# peroherals.net
KiCad netlist of a schematic drawn in Altium Designer
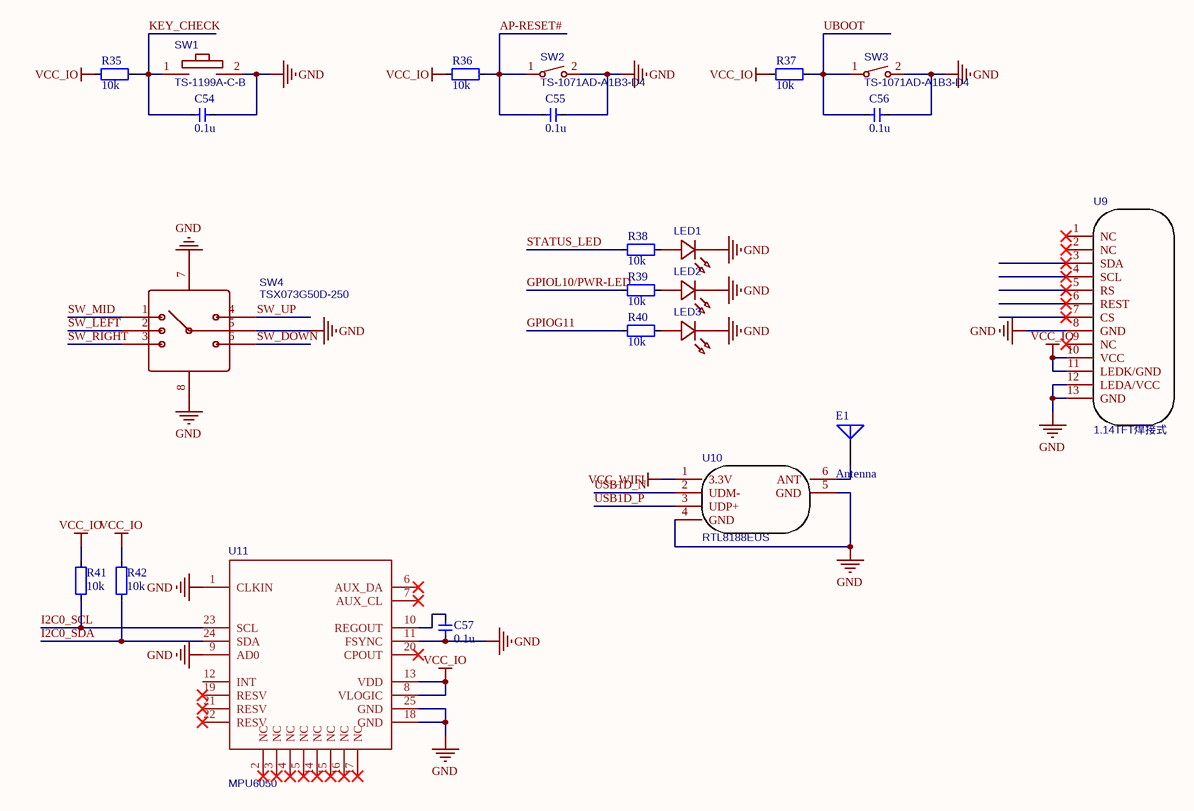
[diagram p0: peroherals.SchDoc]

(export (version "E")
  (design (tool "Eeschema 10.0.6"))
  (components
    (comp (ref "C54")
      (value "0.1u")
      (footprint "C0402")
      (description "Capacitor")
      (fields (field (name "Comment") "CAP-0402"))
      (libsource (lib "core") (part "CAP-0402"))
    )
    (comp (ref "C55")
      (value "0.1u")
      (footprint "C0402")
      (description "Capacitor")
      (fields (field (name "Comment") "CAP-0402"))
      (libsource (lib "core") (part "CAP-0402"))
    )
    (comp (ref "C56")
      (value "0.1u")
      (footprint "C0402")
      (description "Capacitor")
      (fields (field (name "Comment") "CAP-0402"))
      (libsource (lib "core") (part "CAP-0402"))
    )
    (comp (ref "C57")
      (value "0.1u")
      (footprint "C0402")
      (description "Capacitor")
      (fields (field (name "Comment") "CAP-0402"))
      (libsource (lib "core") (part "CAP-0402"))
    )
    (comp (ref "E1")
      (value "Antenna")
      (footprint "PIN1")
      (description "Generic Antenna")
      (fields (field (name "PUBLISHER") "Altium Limited"))
      (libsource (lib "Miscellaneous Devices") (part "Antenna"))
    )
    (comp (ref "LED1")
      (value "TJ-S1005CL4T5ALC6B-A5")
      (footprint "LED0402-RD")
      (fields (field (name "BOM_SUPPLIER PART") "C917189") (field (name "CONTRIBUTOR") "LCSC"))
      (libsource (lib "core") (part "LED-0402"))
    )
    (comp (ref "LED2")
      (value "TJ-S1005CL4T5ALC6B-A5")
      (footprint "LED0402-RD")
      (fields (field (name "BOM_SUPPLIER PART") "C917189") (field (name "CONTRIBUTOR") "LCSC"))
      (libsource (lib "core") (part "LED-0402"))
    )
    (comp (ref "LED3")
      (value "TJ-S1005CL4T5ALC6B-A5")
      (footprint "LED0402-RD")
      (fields (field (name "BOM_SUPPLIER PART") "C917189") (field (name "CONTRIBUTOR") "LCSC"))
      (libsource (lib "core") (part "LED-0402"))
    )
    (comp (ref "R35")
      (value "10k")
      (footprint "R0402")
      (description "Resistor")
      (fields (field (name "Comment") "RES-0402"))
      (libsource (lib "") (part "RES-0402_1"))
    )
    (comp (ref "R36")
      (value "10k")
      (footprint "R0402")
      (description "Resistor")
      (fields (field (name "Comment") "RES-0402"))
      (libsource (lib "") (part "RES-0402_1"))
    )
    (comp (ref "R37")
      (value "10k")
      (footprint "R0402")
      (description "Resistor")
      (fields (field (name "Comment") "RES-0402"))
      (libsource (lib "") (part "RES-0402_1"))
    )
    (comp (ref "R38")
      (value "10k")
      (footprint "R0402")
      (description "Resistor")
      (fields (field (name "Comment") "RES-0402"))
      (libsource (lib "") (part "RES-0402_1"))
    )
    (comp (ref "R39")
      (value "10k")
      (footprint "R0402")
      (description "Resistor")
      (fields (field (name "Comment") "RES-0402"))
      (libsource (lib "") (part "RES-0402_1"))
    )
    (comp (ref "R40")
      (value "10k")
      (footprint "R0402")
      (description "Resistor")
      (fields (field (name "Comment") "RES-0402"))
      (libsource (lib "") (part "RES-0402_1"))
    )
    (comp (ref "R41")
      (value "10k")
      (footprint "R0402")
      (description "Resistor")
      (fields (field (name "Comment") "RES-0402"))
      (libsource (lib "core") (part "RES-0402"))
    )
    (comp (ref "R42")
      (value "10k")
      (footprint "R0402")
      (description "Resistor")
      (fields (field (name "Comment") "RES-0402"))
      (libsource (lib "core") (part "RES-0402"))
    )
    (comp (ref "SW1")
      (value "TS-1199A-C-B")
      (footprint "KEY-SMD_2P-L6.0-W6.0-P6.50")
      (fields (field (name "BOM_SUPPLIER PART") "C318880") (field (name "CONTRIBUTOR") "LCSC"))
      (libsource (lib "core") (part "TS-1199A-C-B"))
    )
    (comp (ref "SW2")
      (value "TS-1071AD-A1B3-D4")
      (footprint "ButtonTACT_3x4x2_180")
      (fields (field (name "BOM_SUPPLIER PART") "C492878") (field (name "CONTRIBUTOR") "LCSC"))
      (libsource (lib "core") (part "TS-1071AD-A1B3-D4"))
    )
    (comp (ref "SW3")
      (value "TS-1071AD-A1B3-D4")
      (footprint "ButtonTACT_3x4x2_180")
      (fields (field (name "BOM_SUPPLIER PART") "C492878") (field (name "CONTRIBUTOR") "LCSC"))
      (libsource (lib "core") (part "TS-1071AD-A1B3-D4"))
    )
    (comp (ref "SW4")
      (value "TSX073G50D-250")
      (footprint "SW-SMD_TSX073G50D1-250")
      (fields (field (name "BOM_SUPPLIER PART") "C722953") (field (name "CONTRIBUTOR") "LCSC"))
      (libsource (lib "core") (part "TSX073G50D-250"))
    )
    (comp (ref "U9")
      (value "1.14TFT焊接式")
      (footprint "1.14TFT焊接式B")
      (fields (field (name "BOM_MANUFACTURER PART") "1.14寸LCD") (field (name "CONTRIBUTOR") "lanlanzhilian"))
      (libsource (lib "core") (part "1.14TFT焊接式"))
    )
    (comp (ref "U10")
      (value "RTL8188EUS")
      (footprint "USB-WIFI-ANT")
      (fields (field (name "CONTRIBUTOR") "Robin00"))
      (libsource (lib "core") (part "RTL8188EUS"))
    )
    (comp (ref "U11")
      (value "MPU6050")
      (footprint "QFN50P400X400X95-25T265X275N")
      (libsource (lib "core") (part "MPU6050"))
    )
  )
  (nets
    (net (code "1") (name "/AP-RESET#") (class "Default")
      (node (ref "C55") (pin "2") (pinfunction "2_2") (pintype "passive"))
      (node (ref "R36") (pin "1") (pinfunction "1_1") (pintype "passive"))
      (node (ref "SW2") (pin "1") (pinfunction "1_1") (pintype "passive"))
    )
    (net (code "2") (name "/GPIOG11") (class "Default")
      (node (ref "R40") (pin "2") (pinfunction "2_2") (pintype "passive"))
    )
    (net (code "3") (name "/GPIOL10{slash}PWR-LED") (class "Default")
      (node (ref "R39") (pin "2") (pinfunction "2_2") (pintype "passive"))
    )
    (net (code "4") (name "/I2C0_SCL") (class "Default")
      (node (ref "R41") (pin "2") (pinfunction "2_2") (pintype "passive"))
      (node (ref "U11") (pin "23") (pinfunction "SCL_23") (pintype "passive"))
    )
    (net (code "5") (name "/I2C0_SDA") (class "Default")
      (node (ref "R42") (pin "2") (pinfunction "2_2") (pintype "passive"))
      (node (ref "U11") (pin "24") (pinfunction "SDA_24") (pintype "passive"))
    )
    (net (code "6") (name "/KEY_CHECK") (class "Default")
      (node (ref "C54") (pin "2") (pinfunction "2_2") (pintype "passive"))
      (node (ref "R35") (pin "1") (pinfunction "1_1") (pintype "passive"))
      (node (ref "SW1") (pin "1") (pinfunction "1_1") (pintype "passive"))
    )
    (net (code "7") (name "/STATUS_LED") (class "Default")
      (node (ref "R38") (pin "2") (pinfunction "2_2") (pintype "passive"))
    )
    (net (code "8") (name "/SW_DOWN") (class "Default")
      (node (ref "SW4") (pin "6") (pinfunction "C_6") (pintype "passive"))
    )
    (net (code "9") (name "/SW_LEFT") (class "Default")
      (node (ref "SW4") (pin "2") (pinfunction "CENTER_2") (pintype "passive"))
    )
    (net (code "10") (name "/SW_MID") (class "Default")
      (node (ref "SW4") (pin "1") (pinfunction "A_1") (pintype "passive"))
    )
    (net (code "11") (name "/SW_RIGHT") (class "Default")
      (node (ref "SW4") (pin "3") (pinfunction "B_3") (pintype "passive"))
    )
    (net (code "12") (name "/SW_UP") (class "Default")
      (node (ref "SW4") (pin "4") (pinfunction "D_4") (pintype "passive"))
    )
    (net (code "13") (name "/UBOOT") (class "Default")
      (node (ref "C56") (pin "2") (pinfunction "2_2") (pintype "passive"))
      (node (ref "R37") (pin "1") (pinfunction "1_1") (pintype "passive"))
      (node (ref "SW3") (pin "1") (pinfunction "1_1") (pintype "passive"))
    )
    (net (code "14") (name "/USB1D_N") (class "Default")
      (node (ref "U10") (pin "2") (pinfunction "UDM-_2") (pintype "passive"))
    )
    (net (code "15") (name "/USB1D_P") (class "Default")
      (node (ref "U10") (pin "3") (pinfunction "UDP+_3") (pintype "passive"))
    )
    (net (code "16") (name "GND") (class "Default")
      (node (ref "C54") (pin "1") (pinfunction "1_1") (pintype "passive"))
      (node (ref "C55") (pin "1") (pinfunction "1_1") (pintype "passive"))
      (node (ref "C56") (pin "1") (pinfunction "1_1") (pintype "passive"))
      (node (ref "C57") (pin "2") (pinfunction "2_2") (pintype "passive"))
      (node (ref "LED1") (pin "1") (pinfunction "K_1") (pintype "passive"))
      (node (ref "LED2") (pin "1") (pinfunction "K_1") (pintype "passive"))
      (node (ref "LED3") (pin "1") (pinfunction "K_1") (pintype "passive"))
      (node (ref "SW1") (pin "2") (pinfunction "2_2") (pintype "passive"))
      (node (ref "SW2") (pin "2") (pinfunction "2_2") (pintype "passive"))
      (node (ref "SW3") (pin "2") (pinfunction "2_2") (pintype "passive"))
      (node (ref "SW4") (pin "5") (pinfunction "COM_5") (pintype "passive"))
      (node (ref "SW4") (pin "7") (pinfunction "GND_7") (pintype "passive"))
      (node (ref "SW4") (pin "8") (pinfunction "GND_8") (pintype "passive"))
      (node (ref "U10") (pin "4") (pinfunction "GND_4") (pintype "passive"))
      (node (ref "U10") (pin "5") (pinfunction "GND_5") (pintype "passive"))
      (node (ref "U11") (pin "1") (pinfunction "CLKIN_1") (pintype "passive"))
      (node (ref "U11") (pin "11") (pinfunction "FSYNC_11") (pintype "passive"))
      (node (ref "U11") (pin "18") (pinfunction "GND_18") (pintype "passive"))
      (node (ref "U11") (pin "25") (pinfunction "GND_25") (pintype "passive"))
      (node (ref "U11") (pin "9") (pinfunction "AD0_9") (pintype "passive"))
      (node (ref "U9") (pin "12") (pinfunction "LEDA/VCC_12") (pintype "passive"))
      (node (ref "U9") (pin "13") (pinfunction "GND_13") (pintype "passive"))
      (node (ref "U9") (pin "8") (pinfunction "GND_8") (pintype "passive"))
    )
    (net (code "17") (name "Net-(E1-A)") (class "Default")
      (node (ref "E1") (pin "1") (pinfunction "A_1") (pintype "passive"))
      (node (ref "U10") (pin "6") (pinfunction "ANT_6") (pintype "passive"))
    )
    (net (code "18") (name "Net-(LED1-A)") (class "Default")
      (node (ref "LED1") (pin "2") (pinfunction "A_2") (pintype "passive"))
      (node (ref "R38") (pin "1") (pinfunction "1_1") (pintype "passive"))
    )
    (net (code "19") (name "Net-(LED2-A)") (class "Default")
      (node (ref "LED2") (pin "2") (pinfunction "A_2") (pintype "passive"))
      (node (ref "R39") (pin "1") (pinfunction "1_1") (pintype "passive"))
    )
    (net (code "20") (name "Net-(LED3-A)") (class "Default")
      (node (ref "LED3") (pin "2") (pinfunction "A_2") (pintype "passive"))
      (node (ref "R40") (pin "1") (pinfunction "1_1") (pintype "passive"))
    )
    (net (code "21") (name "Net-(U11-REGOUT)") (class "Default")
      (node (ref "C57") (pin "1") (pinfunction "1_1") (pintype "passive"))
      (node (ref "U11") (pin "10") (pinfunction "REGOUT_10") (pintype "passive"))
    )
    (net (code "22") (name "VCC_IO") (class "Default")
      (node (ref "R35") (pin "2") (pinfunction "2_2") (pintype "passive"))
      (node (ref "R36") (pin "2") (pinfunction "2_2") (pintype "passive"))
      (node (ref "R37") (pin "2") (pinfunction "2_2") (pintype "passive"))
      (node (ref "R41") (pin "1") (pinfunction "1_1") (pintype "passive"))
      (node (ref "R42") (pin "1") (pinfunction "1_1") (pintype "passive"))
      (node (ref "U11") (pin "13") (pinfunction "VDD_13") (pintype "passive"))
      (node (ref "U11") (pin "8") (pinfunction "VLOGIC_8") (pintype "passive"))
      (node (ref "U9") (pin "10") (pinfunction "VCC_10") (pintype "passive"))
      (node (ref "U9") (pin "11") (pinfunction "LEDK/GND_11") (pintype "passive"))
    )
    (net (code "23") (name "VCC_WIFI") (class "Default")
      (node (ref "U10") (pin "1") (pinfunction "3.3V_1") (pintype "passive"))
    )
    (net (code "24") (name "unconnected-(U9-CS-Pad7)") (class "Default")
      (node (ref "U9") (pin "7") (pinfunction "CS_7") (pintype "passive+no_connect"))
    )
    (net (code "25") (name "unconnected-(U9-NC-Pad1)") (class "Default")
      (node (ref "U9") (pin "1") (pinfunction "NC_1") (pintype "passive+no_connect"))
    )
    (net (code "26") (name "unconnected-(U9-NC-Pad2)") (class "Default")
      (node (ref "U9") (pin "2") (pinfunction "NC_2") (pintype "passive+no_connect"))
    )
    (net (code "27") (name "unconnected-(U9-NC-Pad9)") (class "Default")
      (node (ref "U9") (pin "9") (pinfunction "NC_9") (pintype "passive+no_connect"))
    )
    (net (code "28") (name "unconnected-(U9-REST-Pad6)") (class "Default")
      (node (ref "U9") (pin "6") (pinfunction "REST_6") (pintype "passive+no_connect"))
    )
    (net (code "29") (name "unconnected-(U9-RS-Pad5)") (class "Default")
      (node (ref "U9") (pin "5") (pinfunction "RS_5") (pintype "passive+no_connect"))
    )
    (net (code "30") (name "unconnected-(U9-SCL-Pad4)") (class "Default")
      (node (ref "U9") (pin "4") (pinfunction "SCL_4") (pintype "passive+no_connect"))
    )
    (net (code "31") (name "unconnected-(U9-SDA-Pad3)") (class "Default")
      (node (ref "U9") (pin "3") (pinfunction "SDA_3") (pintype "passive+no_connect"))
    )
    (net (code "32") (name "unconnected-(U11-AUX_CL-Pad7)") (class "Default")
      (node (ref "U11") (pin "7") (pinfunction "AUX_CL_7") (pintype "passive+no_connect"))
    )
    (net (code "33") (name "unconnected-(U11-AUX_DA-Pad6)") (class "Default")
      (node (ref "U11") (pin "6") (pinfunction "AUX_DA_6") (pintype "passive+no_connect"))
    )
    (net (code "34") (name "unconnected-(U11-CPOUT-Pad20)") (class "Default")
      (node (ref "U11") (pin "20") (pinfunction "CPOUT_20") (pintype "passive+no_connect"))
    )
    (net (code "35") (name "unconnected-(U11-INT-Pad12)") (class "Default")
      (node (ref "U11") (pin "12") (pinfunction "INT_12") (pintype "passive"))
    )
    (net (code "36") (name "unconnected-(U11-NC-Pad2)") (class "Default")
      (node (ref "U11") (pin "2") (pinfunction "NC_2") (pintype "passive+no_connect"))
    )
    (net (code "37") (name "unconnected-(U11-NC-Pad3)") (class "Default")
      (node (ref "U11") (pin "3") (pinfunction "NC_3") (pintype "passive+no_connect"))
    )
    (net (code "38") (name "unconnected-(U11-NC-Pad4)") (class "Default")
      (node (ref "U11") (pin "4") (pinfunction "NC_4") (pintype "passive+no_connect"))
    )
    (net (code "39") (name "unconnected-(U11-NC-Pad5)") (class "Default")
      (node (ref "U11") (pin "5") (pinfunction "NC_5") (pintype "passive+no_connect"))
    )
    (net (code "40") (name "unconnected-(U11-NC-Pad14)") (class "Default")
      (node (ref "U11") (pin "14") (pinfunction "NC_14") (pintype "passive+no_connect"))
    )
    (net (code "41") (name "unconnected-(U11-NC-Pad15)") (class "Default")
      (node (ref "U11") (pin "15") (pinfunction "NC_15") (pintype "passive+no_connect"))
    )
    (net (code "42") (name "unconnected-(U11-NC-Pad16)") (class "Default")
      (node (ref "U11") (pin "16") (pinfunction "NC_16") (pintype "passive+no_connect"))
    )
    (net (code "43") (name "unconnected-(U11-NC-Pad17)") (class "Default")
      (node (ref "U11") (pin "17") (pinfunction "NC_17") (pintype "passive+no_connect"))
    )
    (net (code "44") (name "unconnected-(U11-RESV-Pad19)") (class "Default")
      (node (ref "U11") (pin "19") (pinfunction "RESV_19") (pintype "passive+no_connect"))
    )
    (net (code "45") (name "unconnected-(U11-RESV-Pad21)") (class "Default")
      (node (ref "U11") (pin "21") (pinfunction "RESV_21") (pintype "passive+no_connect"))
    )
    (net (code "46") (name "unconnected-(U11-RESV-Pad22)") (class "Default")
      (node (ref "U11") (pin "22") (pinfunction "RESV_22") (pintype "passive+no_connect"))
    )
  )
)
